# R3D2_long_range.net
KiCad netlist of a schematic drawn in EAGLE
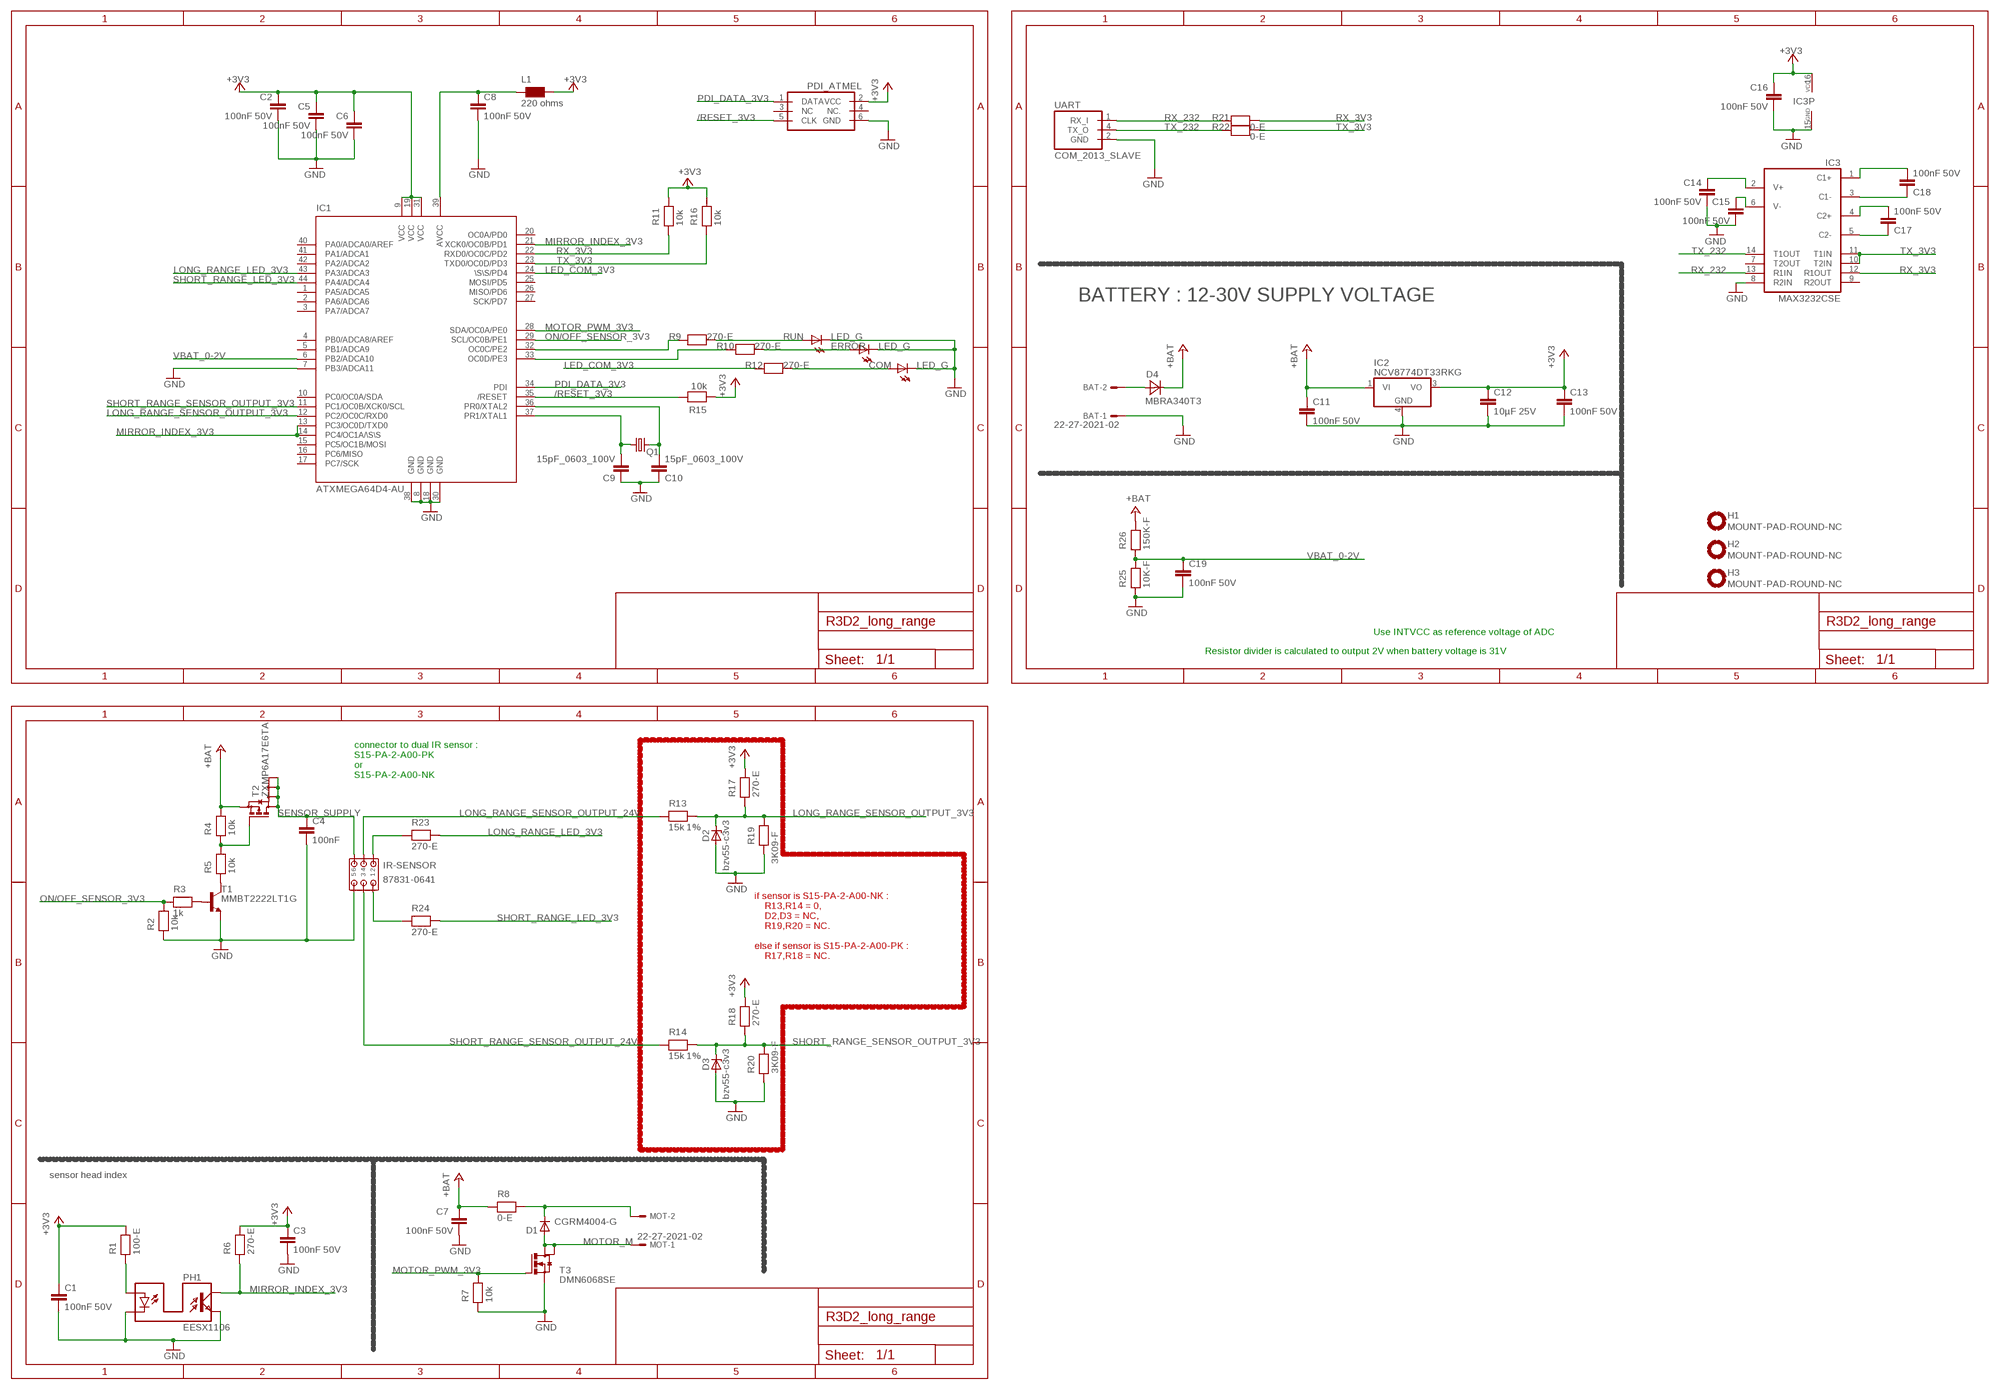
[diagram p0: schematic, sheet 1]

(export (version "E")
  (design (tool "Eeschema 10.0.6"))
  (components
    (comp (ref "BAT")
      (value "22-27-2021-02")
      (footprint "eagle-import:6410-02")
      (libsource (lib "eagle-import") (part "22-?-0227-2021"))
    )
    (comp (ref "C1")
      (value "100nF 50V")
      (footprint "eagle-import:C0603")
      (libsource (lib "eagle-import") (part "100NF-F"))
    )
    (comp (ref "C2")
      (value "100nF 50V")
      (footprint "eagle-import:C0603")
      (libsource (lib "eagle-import") (part "100NF-F"))
    )
    (comp (ref "C3")
      (value "100nF 50V")
      (footprint "eagle-import:C0603")
      (libsource (lib "eagle-import") (part "100NF-F"))
    )
    (comp (ref "C4")
      (value "100nF")
      (footprint "eagle-import:C0603")
      (libsource (lib "eagle-import") (part "100NF-F"))
    )
    (comp (ref "C5")
      (value "100nF 50V")
      (footprint "eagle-import:C0603")
      (libsource (lib "eagle-import") (part "100NF-F"))
    )
    (comp (ref "C6")
      (value "100nF 50V")
      (footprint "eagle-import:C0603")
      (libsource (lib "eagle-import") (part "100NF-F"))
    )
    (comp (ref "C7")
      (value "100nF 50V")
      (footprint "eagle-import:C0603")
      (libsource (lib "eagle-import") (part "100NF-F"))
    )
    (comp (ref "C8")
      (value "100nF 50V")
      (footprint "eagle-import:C0603")
      (libsource (lib "eagle-import") (part "100NF-F"))
    )
    (comp (ref "C9")
      (value "15pF_0603_100V")
      (footprint "eagle-import:C0603")
      (libsource (lib "eagle-import") (part "15PF-F"))
    )
    (comp (ref "C10")
      (value "15pF_0603_100V")
      (footprint "eagle-import:C0603")
      (libsource (lib "eagle-import") (part "15PF-F"))
    )
    (comp (ref "C11")
      (value "100nF 50V")
      (footprint "eagle-import:C0805")
      (libsource (lib "eagle-import") (part "100NF-E"))
    )
    (comp (ref "C12")
      (value "10µF 25V")
      (footprint "eagle-import:C1210")
      (libsource (lib "eagle-import") (part "10UF-C_25V"))
    )
    (comp (ref "C13")
      (value "100nF 50V")
      (footprint "eagle-import:C0603")
      (libsource (lib "eagle-import") (part "100NF-F"))
    )
    (comp (ref "C14")
      (value "100nF 50V")
      (footprint "eagle-import:C0603")
      (libsource (lib "eagle-import") (part "100NF-F"))
    )
    (comp (ref "C15")
      (value "100nF 50V")
      (footprint "eagle-import:C0603")
      (libsource (lib "eagle-import") (part "100NF-F"))
    )
    (comp (ref "C16")
      (value "100nF 50V")
      (footprint "eagle-import:C0603")
      (libsource (lib "eagle-import") (part "100NF-F"))
    )
    (comp (ref "C17")
      (value "100nF 50V")
      (footprint "eagle-import:C0603")
      (libsource (lib "eagle-import") (part "100NF-F"))
    )
    (comp (ref "C18")
      (value "100nF 50V")
      (footprint "eagle-import:C0603")
      (libsource (lib "eagle-import") (part "100NF-F"))
    )
    (comp (ref "C19")
      (value "100nF 50V")
      (footprint "eagle-import:C0805")
      (libsource (lib "eagle-import") (part "100NF-E"))
    )
    (comp (ref "COM")
      (value "LED_G")
      (footprint "eagle-import:CHIP-LED0805")
      (libsource (lib "eagle-import") (part "LED_G"))
    )
    (comp (ref "D1")
      (value "CGRM4004-G")
      (footprint "eagle-import:SOD-123_MINI-SMA")
      (libsource (lib "eagle-import") (part "CGRM400-G4"))
    )
    (comp (ref "D2")
      (value "bzv55-c3v3")
      (footprint "eagle-import:SOD80C")
      (libsource (lib "eagle-import") (part "BZV55-C3V3SOD80C"))
    )
    (comp (ref "D3")
      (value "bzv55-c3v3")
      (footprint "eagle-import:SOD80C")
      (libsource (lib "eagle-import") (part "BZV55-C3V3SOD80C"))
    )
    (comp (ref "D4")
      (value "MBRA340T3")
      (footprint "eagle-import:SMA")
      (libsource (lib "eagle-import") (part "MBRA340T3"))
    )
    (comp (ref "ERROR")
      (value "LED_G")
      (footprint "eagle-import:CHIP-LED0805")
      (libsource (lib "eagle-import") (part "LED_G"))
    )
    (comp (ref "H1")
      (value "MOUNT-PAD-ROUND-NC")
      (footprint "eagle-import:3,0-PAD_NC")
      (libsource (lib "eagle-import") (part "MOUNT-PAD-ROUND-NC"))
    )
    (comp (ref "H2")
      (value "MOUNT-PAD-ROUND-NC")
      (footprint "eagle-import:3,0-PAD_NC")
      (libsource (lib "eagle-import") (part "MOUNT-PAD-ROUND-NC"))
    )
    (comp (ref "H3")
      (value "MOUNT-PAD-ROUND-NC")
      (footprint "eagle-import:3,0-PAD_NC")
      (libsource (lib "eagle-import") (part "MOUNT-PAD-ROUND-NC"))
    )
    (comp (ref "IC1")
      (value "ATXMEGA64D4-AU")
      (footprint "eagle-import:TQFP44")
      (libsource (lib "eagle-import") (part "ATXMEGA64D4-AU"))
    )
    (comp (ref "IC2")
      (value "NCV8774DT33RKG")
      (footprint "eagle-import:DPACK_3")
      (libsource (lib "eagle-import") (part "NCV8774DT33RKG"))
    )
    (comp (ref "IC3")
      (value "MAX3232CSE")
      (footprint "eagle-import:SO16")
      (libsource (lib "eagle-import") (part "MAX3232SEC"))
    )
    (comp (ref "IR-SENSOR")
      (value "87831-0641")
      (footprint "eagle-import:87831-0641")
      (libsource (lib "eagle-import") (part "87831-0641"))
    )
    (comp (ref "L1")
      (value "220 ohms")
      (footprint "eagle-import:R0603")
      (libsource (lib "eagle-import") (part "FERRITE_220OHMS"))
    )
    (comp (ref "MOT")
      (value "22-27-2021-02")
      (footprint "eagle-import:6410-02")
      (libsource (lib "eagle-import") (part "22-?-0227-2021"))
    )
    (comp (ref "PDI_ATMEL")
      (value "PDI_ATMELL")
      (footprint "eagle-import:ML6L")
      (libsource (lib "eagle-import") (part "PDI_ATMELL"))
    )
    (comp (ref "PH1")
      (value "EESX1106")
      (footprint "eagle-import:EESX1106")
      (libsource (lib "eagle-import") (part "EESX1106"))
    )
    (comp (ref "Q1")
      (value "CRYSTAL_16MHZ_5032")
      (footprint "eagle-import:CRYSTAL_5032")
      (libsource (lib "eagle-import") (part "CRYSTAL_16MHZ_5032"))
    )
    (comp (ref "R1")
      (value "100-E")
      (footprint "eagle-import:R0805")
      (libsource (lib "eagle-import") (part "100-E"))
    )
    (comp (ref "R2")
      (value "10k")
      (footprint "eagle-import:R0603")
      (libsource (lib "eagle-import") (part "10K-F"))
    )
    (comp (ref "R3")
      (value "1k")
      (footprint "eagle-import:R0603")
      (libsource (lib "eagle-import") (part "1K-F"))
    )
    (comp (ref "R4")
      (value "10k")
      (footprint "eagle-import:R0603")
      (libsource (lib "eagle-import") (part "10K-F"))
    )
    (comp (ref "R5")
      (value "10k")
      (footprint "eagle-import:R0603")
      (libsource (lib "eagle-import") (part "10K-F"))
    )
    (comp (ref "R6")
      (value "270-E")
      (footprint "eagle-import:R0805")
      (libsource (lib "eagle-import") (part "270-E"))
    )
    (comp (ref "R7")
      (value "10k")
      (footprint "eagle-import:R0603")
      (libsource (lib "eagle-import") (part "10K-F"))
    )
    (comp (ref "R8")
      (value "0-E")
      (footprint "eagle-import:R0805")
      (libsource (lib "eagle-import") (part "0-E"))
    )
    (comp (ref "R9")
      (value "270-E")
      (footprint "eagle-import:R0805")
      (libsource (lib "eagle-import") (part "270-E"))
    )
    (comp (ref "R10")
      (value "270-E")
      (footprint "eagle-import:R0805")
      (libsource (lib "eagle-import") (part "270-E"))
    )
    (comp (ref "R11")
      (value "10k")
      (footprint "eagle-import:R0603")
      (libsource (lib "eagle-import") (part "10K-F"))
    )
    (comp (ref "R12")
      (value "270-E")
      (footprint "eagle-import:R0805")
      (libsource (lib "eagle-import") (part "270-E"))
    )
    (comp (ref "R13")
      (value "15k 1%")
      (footprint "eagle-import:R0603")
      (libsource (lib "eagle-import") (part "15K-F"))
    )
    (comp (ref "R14")
      (value "15k 1%")
      (footprint "eagle-import:R0603")
      (libsource (lib "eagle-import") (part "15K-F"))
    )
    (comp (ref "R15")
      (value "10k")
      (footprint "eagle-import:R0603")
      (libsource (lib "eagle-import") (part "10K-F"))
    )
    (comp (ref "R16")
      (value "10k")
      (footprint "eagle-import:R0603")
      (libsource (lib "eagle-import") (part "10K-F"))
    )
    (comp (ref "R17")
      (value "270-E")
      (footprint "eagle-import:R0805")
      (libsource (lib "eagle-import") (part "270-E"))
    )
    (comp (ref "R18")
      (value "270-E")
      (footprint "eagle-import:R0805")
      (libsource (lib "eagle-import") (part "270-E"))
    )
    (comp (ref "R19")
      (value "3K09-F")
      (footprint "eagle-import:R0603")
      (libsource (lib "eagle-import") (part "3K09-F"))
    )
    (comp (ref "R20")
      (value "3K09-F")
      (footprint "eagle-import:R0603")
      (libsource (lib "eagle-import") (part "3K09-F"))
    )
    (comp (ref "R21")
      (value "0-E")
      (footprint "eagle-import:R0805")
      (libsource (lib "eagle-import") (part "0-E"))
    )
    (comp (ref "R22")
      (value "0-E")
      (footprint "eagle-import:R0805")
      (libsource (lib "eagle-import") (part "0-E"))
    )
    (comp (ref "R23")
      (value "270-E")
      (footprint "eagle-import:R0805")
      (libsource (lib "eagle-import") (part "270-E"))
    )
    (comp (ref "R24")
      (value "270-E")
      (footprint "eagle-import:R0805")
      (libsource (lib "eagle-import") (part "270-E"))
    )
    (comp (ref "R25")
      (value "10K-F")
      (footprint "eagle-import:R0603")
      (libsource (lib "eagle-import") (part "10K-F"))
    )
    (comp (ref "R26")
      (value "150K-F")
      (footprint "eagle-import:R0603")
      (libsource (lib "eagle-import") (part "150K-F"))
    )
    (comp (ref "RUN")
      (value "LED_G")
      (footprint "eagle-import:CHIP-LED0805")
      (libsource (lib "eagle-import") (part "LED_G"))
    )
    (comp (ref "T1")
      (value "MMBT2222LT1G")
      (footprint "eagle-import:SOT23-BEC")
      (libsource (lib "eagle-import") (part "-NPN-SOT23-BECMMBT2222ALT1"))
    )
    (comp (ref "T2")
      (value "ZXMP6A17E6TA")
      (footprint "eagle-import:SOT26")
      (libsource (lib "eagle-import") (part "ZXMP6A17E6TA"))
    )
    (comp (ref "T3")
      (value "DMN6068SE")
      (footprint "eagle-import:SOT223")
      (libsource (lib "eagle-import") (part "DMN6068SE"))
    )
    (comp (ref "UART")
      (value "COM_2013_SLAVE")
      (footprint "eagle-import:MICROMATCH-4_SMD")
      (libsource (lib "eagle-import") (part "COM_2013_SLAVE"))
    )
  )
  (nets
    (net (code "1") (name "+3V3") (class "Default")
      (node (ref "C1") (pin "1") (pinfunction "1_1") (pintype "passive"))
      (node (ref "C12") (pin "1") (pinfunction "1_1") (pintype "passive"))
      (node (ref "C13") (pin "1") (pinfunction "1_1") (pintype "passive"))
      (node (ref "C16") (pin "1") (pinfunction "1_1") (pintype "passive"))
      (node (ref "C2") (pin "1") (pinfunction "1_1") (pintype "passive"))
      (node (ref "C3") (pin "1") (pinfunction "1_1") (pintype "passive"))
      (node (ref "C5") (pin "1") (pinfunction "1_1") (pintype "passive"))
      (node (ref "C6") (pin "1") (pinfunction "1_1") (pintype "passive"))
      (node (ref "IC1") (pin "19") (pinfunction "VCC_19") (pintype "bidirectional"))
      (node (ref "IC1") (pin "31") (pinfunction "VCC_31") (pintype "bidirectional"))
      (node (ref "IC1") (pin "9") (pinfunction "VCC_9") (pintype "bidirectional"))
      (node (ref "IC2") (pin "3") (pinfunction "VO_3") (pintype "passive"))
      (node (ref "IC3") (pin "16") (pinfunction "VCC_16") (pintype "power_in"))
      (node (ref "L1") (pin "2") (pinfunction "2_2") (pintype "passive"))
      (node (ref "PDI_ATMEL") (pin "2") (pinfunction "VCC_2") (pintype "passive"))
      (node (ref "R1") (pin "2") (pinfunction "2_2") (pintype "bidirectional"))
      (node (ref "R11") (pin "2") (pinfunction "2_2") (pintype "bidirectional"))
      (node (ref "R15") (pin "1") (pinfunction "1_1") (pintype "bidirectional"))
      (node (ref "R16") (pin "2") (pinfunction "2_2") (pintype "bidirectional"))
      (node (ref "R17") (pin "2") (pinfunction "2_2") (pintype "bidirectional"))
      (node (ref "R18") (pin "2") (pinfunction "2_2") (pintype "bidirectional"))
      (node (ref "R6") (pin "2") (pinfunction "2_2") (pintype "bidirectional"))
    )
    (net (code "2") (name "+BAT") (class "Default")
      (node (ref "C11") (pin "1") (pinfunction "1_1") (pintype "passive"))
      (node (ref "C7") (pin "1") (pinfunction "1_1") (pintype "passive"))
      (node (ref "D4") (pin "C") (pinfunction "C_C") (pintype "passive"))
      (node (ref "IC2") (pin "1") (pinfunction "VI_1") (pintype "input"))
      (node (ref "R26") (pin "2") (pinfunction "2_2") (pintype "bidirectional"))
      (node (ref "R4") (pin "2") (pinfunction "2_2") (pintype "bidirectional"))
      (node (ref "R8") (pin "1") (pinfunction "1_1") (pintype "bidirectional"))
      (node (ref "T2") (pin "4") (pinfunction "S_4") (pintype "passive"))
    )
    (net (code "3") (name "/LED_COM_3V3") (class "Default")
      (node (ref "IC1") (pin "24") (pinfunction "\\S\\S/PD4_24") (pintype "bidirectional"))
      (node (ref "R12") (pin "1") (pinfunction "1_1") (pintype "bidirectional"))
    )
    (net (code "4") (name "/LONG_RANGE_LED_3V3") (class "Default")
      (node (ref "IC1") (pin "43") (pinfunction "PA3/ADCA3_43") (pintype "bidirectional"))
      (node (ref "R23") (pin "2") (pinfunction "2_2") (pintype "bidirectional"))
    )
    (net (code "5") (name "/LONG_RANGE_SENSOR_OUTPUT_3V3") (class "Default")
      (node (ref "D2") (pin "C") (pinfunction "C_C") (pintype "passive"))
      (node (ref "IC1") (pin "12") (pinfunction "PC2/OC0C/RXD0_12") (pintype "bidirectional"))
      (node (ref "R13") (pin "2") (pinfunction "2_2") (pintype "bidirectional"))
      (node (ref "R17") (pin "1") (pinfunction "1_1") (pintype "bidirectional"))
      (node (ref "R19") (pin "2") (pinfunction "2_2") (pintype "bidirectional"))
    )
    (net (code "6") (name "/LONG_RANGE_SENSOR_OUTPUT_24V") (class "Default")
      (node (ref "IR-SENSOR") (pin "4") (pinfunction "4_4") (pintype "passive"))
      (node (ref "R13") (pin "1") (pinfunction "1_1") (pintype "bidirectional"))
    )
    (net (code "7") (name "/MIRROR_INDEX_3V3") (class "Default")
      (node (ref "IC1") (pin "13") (pinfunction "PC3/OC0D/TXD0_13") (pintype "bidirectional"))
      (node (ref "IC1") (pin "14") (pinfunction "PC4/OC1A/\\S\\S_14") (pintype "bidirectional"))
      (node (ref "IC1") (pin "21") (pinfunction "XCK0/OC0B/PD1_21") (pintype "bidirectional"))
      (node (ref "PH1") (pin "C") (pinfunction "TRANSISTOR_C_C") (pintype "passive"))
      (node (ref "R6") (pin "1") (pinfunction "1_1") (pintype "bidirectional"))
    )
    (net (code "8") (name "/MOTOR_M") (class "Default")
      (node (ref "D1") (pin "A") (pinfunction "A_A") (pintype "passive"))
      (node (ref "MOT") (pin "1") (pinfunction "S_1") (pintype "passive"))
      (node (ref "T3") (pin "2") (pinfunction "D_2") (pintype "passive"))
      (node (ref "T3") (pin "4") (pinfunction "D_4") (pintype "passive"))
    )
    (net (code "9") (name "/MOTOR_PWM_3V3") (class "Default")
      (node (ref "IC1") (pin "28") (pinfunction "SDA/OC0A/PE0_28") (pintype "bidirectional"))
      (node (ref "R7") (pin "2") (pinfunction "2_2") (pintype "bidirectional"))
      (node (ref "T3") (pin "1") (pinfunction "G_1") (pintype "passive"))
    )
    (net (code "10") (name "/ON{slash}OFF_SENSOR_3V3") (class "Default")
      (node (ref "IC1") (pin "29") (pinfunction "SCL/OC0B/PE1_29") (pintype "bidirectional"))
      (node (ref "R2") (pin "2") (pinfunction "2_2") (pintype "bidirectional"))
      (node (ref "R3") (pin "1") (pinfunction "1_1") (pintype "bidirectional"))
    )
    (net (code "11") (name "/PDI_DATA_3V3") (class "Default")
      (node (ref "IC1") (pin "34") (pinfunction "PDI_34") (pintype "bidirectional"))
      (node (ref "PDI_ATMEL") (pin "1") (pinfunction "DATA_1") (pintype "passive"))
    )
    (net (code "12") (name "/RX_3V3") (class "Default")
      (node (ref "IC1") (pin "22") (pinfunction "RXD0/OC0C/PD2_22") (pintype "bidirectional"))
      (node (ref "IC3") (pin "12") (pinfunction "R1OUT_12") (pintype "output"))
      (node (ref "R11") (pin "1") (pinfunction "1_1") (pintype "bidirectional"))
      (node (ref "R21") (pin "2") (pinfunction "2_2") (pintype "bidirectional"))
    )
    (net (code "13") (name "/RX_232") (class "Default")
      (node (ref "IC3") (pin "13") (pinfunction "R1IN_13") (pintype "input"))
      (node (ref "R21") (pin "1") (pinfunction "1_1") (pintype "bidirectional"))
      (node (ref "UART") (pin "1") (pinfunction "RX_I_1") (pintype "passive"))
    )
    (net (code "14") (name "/SENSOR_SUPPLY") (class "Default")
      (node (ref "C4") (pin "1") (pinfunction "1_1") (pintype "passive"))
      (node (ref "IR-SENSOR") (pin "6") (pinfunction "6_6") (pintype "passive"))
      (node (ref "T2") (pin "1") (pinfunction "D_1") (pintype "passive"))
      (node (ref "T2") (pin "2") (pinfunction "D_2") (pintype "passive"))
      (node (ref "T2") (pin "5") (pinfunction "D_5") (pintype "passive"))
      (node (ref "T2") (pin "6") (pinfunction "D_6") (pintype "passive"))
    )
    (net (code "15") (name "/SHORT_RANGE_LED_3V3") (class "Default")
      (node (ref "IC1") (pin "44") (pinfunction "PA4/ADCA4_44") (pintype "bidirectional"))
      (node (ref "R24") (pin "2") (pinfunction "2_2") (pintype "bidirectional"))
    )
    (net (code "16") (name "/SHORT_RANGE_SENSOR_OUTPUT_3V3") (class "Default")
      (node (ref "D3") (pin "C") (pinfunction "C_C") (pintype "passive"))
      (node (ref "IC1") (pin "11") (pinfunction "PC1/OC0B/XCK0/SCL_11") (pintype "bidirectional"))
      (node (ref "R14") (pin "2") (pinfunction "2_2") (pintype "bidirectional"))
      (node (ref "R18") (pin "1") (pinfunction "1_1") (pintype "bidirectional"))
      (node (ref "R20") (pin "2") (pinfunction "2_2") (pintype "bidirectional"))
    )
    (net (code "17") (name "/SHORT_RANGE_SENSOR_OUTPUT_24V") (class "Default")
      (node (ref "IR-SENSOR") (pin "3") (pinfunction "3_3") (pintype "passive"))
      (node (ref "R14") (pin "1") (pinfunction "1_1") (pintype "bidirectional"))
    )
    (net (code "18") (name "/TX_3V3") (class "Default")
      (node (ref "IC1") (pin "23") (pinfunction "TXD0/OC0D/PD3_23") (pintype "bidirectional"))
      (node (ref "IC3") (pin "10") (pinfunction "T2IN_10") (pintype "input"))
      (node (ref "IC3") (pin "11") (pinfunction "T1IN_11") (pintype "input"))
      (node (ref "R16") (pin "1") (pinfunction "1_1") (pintype "bidirectional"))
      (node (ref "R22") (pin "2") (pinfunction "2_2") (pintype "bidirectional"))
    )
    (net (code "19") (name "/TX_232") (class "Default")
      (node (ref "IC3") (pin "14") (pinfunction "T1OUT_14") (pintype "output"))
      (node (ref "R22") (pin "1") (pinfunction "1_1") (pintype "bidirectional"))
      (node (ref "UART") (pin "4") (pinfunction "TX_O_4") (pintype "passive"))
    )
    (net (code "20") (name "/VBAT_0-2V") (class "Default")
      (node (ref "C19") (pin "1") (pinfunction "1_1") (pintype "passive"))
      (node (ref "IC1") (pin "6") (pinfunction "PB2/ADCA10_6") (pintype "bidirectional"))
      (node (ref "R25") (pin "2") (pinfunction "2_2") (pintype "bidirectional"))
      (node (ref "R26") (pin "1") (pinfunction "1_1") (pintype "bidirectional"))
    )
    (net (code "21") (name "/{slash}RESET_3V3") (class "Default")
      (node (ref "IC1") (pin "35") (pinfunction "/RESET_35") (pintype "bidirectional"))
      (node (ref "PDI_ATMEL") (pin "5") (pinfunction "CLK_5") (pintype "passive"))
      (node (ref "R15") (pin "2") (pinfunction "2_2") (pintype "bidirectional"))
    )
    (net (code "22") (name "GND") (class "Default")
      (node (ref "BAT") (pin "1") (pinfunction "S_1") (pintype "passive"))
      (node (ref "C1") (pin "2") (pinfunction "2_2") (pintype "passive"))
      (node (ref "C10") (pin "1") (pinfunction "1_1") (pintype "passive"))
      (node (ref "C11") (pin "2") (pinfunction "2_2") (pintype "passive"))
      (node (ref "C12") (pin "2") (pinfunction "2_2") (pintype "passive"))
      (node (ref "C13") (pin "2") (pinfunction "2_2") (pintype "passive"))
      (node (ref "C14") (pin "2") (pinfunction "2_2") (pintype "passive"))
      (node (ref "C15") (pin "2") (pinfunction "2_2") (pintype "passive"))
      (node (ref "C16") (pin "2") (pinfunction "2_2") (pintype "passive"))
      (node (ref "C19") (pin "2") (pinfunction "2_2") (pintype "passive"))
      (node (ref "C2") (pin "2") (pinfunction "2_2") (pintype "passive"))
      (node (ref "C3") (pin "2") (pinfunction "2_2") (pintype "passive"))
      (node (ref "C4") (pin "2") (pinfunction "2_2") (pintype "passive"))
      (node (ref "C5") (pin "2") (pinfunction "2_2") (pintype "passive"))
      (node (ref "C6") (pin "2") (pinfunction "2_2") (pintype "passive"))
      (node (ref "C7") (pin "2") (pinfunction "2_2") (pintype "passive"))
      (node (ref "C8") (pin "2") (pinfunction "2_2") (pintype "passive"))
      (node (ref "C9") (pin "1") (pinfunction "1_1") (pintype "passive"))
      (node (ref "COM") (pin "C") (pinfunction "C_C") (pintype "passive"))
      (node (ref "D2") (pin "A") (pinfunction "A_A") (pintype "passive"))
      (node (ref "D3") (pin "A") (pinfunction "A_A") (pintype "passive"))
      (node (ref "ERROR") (pin "C") (pinfunction "C_C") (pintype "passive"))
      (node (ref "IC1") (pin "18") (pinfunction "GND_18") (pintype "bidirectional"))
      (node (ref "IC1") (pin "30") (pinfunction "GND_30") (pintype "bidirectional"))
      (node (ref "IC1") (pin "38") (pinfunction "GND_38") (pintype "bidirectional"))
      (node (ref "IC1") (pin "7") (pinfunction "PB3/ADCA11_7") (pintype "bidirectional"))
      (node (ref "IC1") (pin "8") (pinfunction "GND_8") (pintype "bidirectional"))
      (node (ref "IC2") (pin "4") (pinfunction "GND_4") (pintype "passive"))
      (node (ref "IC3") (pin "15") (pinfunction "GND_15") (pintype "power_in"))
      (node (ref "IC3") (pin "8") (pinfunction "R2IN_8") (pintype "input"))
      (node (ref "IR-SENSOR") (pin "5") (pinfunction "5_5") (pintype "passive"))
      (node (ref "PDI_ATMEL") (pin "6") (pinfunction "GND_6") (pintype "passive"))
      (node (ref "PH1") (pin "E") (pinfunction "TRANSISTOR_E_E") (pintype "passive"))
      (node (ref "PH1") (pin "K") (pinfunction "LED_C_K") (pintype "passive"))
      (node (ref "R19") (pin "1") (pinfunction "1_1") (pintype "bidirectional"))
      (node (ref "R2") (pin "1") (pinfunction "1_1") (pintype "bidirectional"))
      (node (ref "R20") (pin "1") (pinfunction "1_1") (pintype "bidirectional"))
      (node (ref "R25") (pin "1") (pinfunction "1_1") (pintype "bidirectional"))
      (node (ref "R7") (pin "1") (pinfunction "1_1") (pintype "bidirectional"))
      (node (ref "RUN") (pin "C") (pinfunction "C_C") (pintype "passive"))
      (node (ref "T1") (pin "E") (pinfunction "E_E") (pintype "passive"))
      (node (ref "T3") (pin "3") (pinfunction "S_3") (pintype "passive"))
      (node (ref "UART") (pin "2") (pinfunction "GND_2") (pintype "passive"))
    )
    (net (code "23") (name "Net-(BATB-S)") (class "Default")
      (node (ref "BAT") (pin "2") (pinfunction "S_2") (pintype "passive"))
      (node (ref "D4") (pin "A") (pinfunction "A_A") (pintype "passive"))
    )
    (net (code "24") (name "Net-(COM-PadA)") (class "Default")
      (node (ref "COM") (pin "A") (pinfunction "A_A") (pintype "passive"))
      (node (ref "R12") (pin "2") (pinfunction "2_2") (pintype "bidirectional"))
    )
    (net (code "25") (name "Net-(ERROR-PadA)") (class "Default")
      (node (ref "ERROR") (pin "A") (pinfunction "A_A") (pintype "passive"))
      (node (ref "R10") (pin "2") (pinfunction "2_2") (pintype "bidirectional"))
    )
    (net (code "26") (name "Net-(IC1-AVCC)") (class "Default")
      (node (ref "C8") (pin "1") (pinfunction "1_1") (pintype "passive"))
      (node (ref "IC1") (pin "39") (pinfunction "AVCC_39") (pintype "bidirectional"))
      (node (ref "L1") (pin "1") (pinfunction "1_1") (pintype "passive"))
    )
    (net (code "27") (name "Net-(IC1-OC0C{slash}PE2)") (class "Default")
      (node (ref "IC1") (pin "32") (pinfunction "OC0C/PE2_32") (pintype "bidirectional"))
      (node (ref "R9") (pin "1") (pinfunction "1_1") (pintype "bidirectional"))
    )
    (net (code "28") (name "Net-(IC1-OC0D{slash}PE3)") (class "Default")
      (node (ref "IC1") (pin "33") (pinfunction "OC0D/PE3_33") (pintype "bidirectional"))
      (node (ref "R10") (pin "1") (pinfunction "1_1") (pintype "bidirectional"))
    )
    (net (code "29") (name "Net-(IC1-PR0{slash}XTAL2)") (class "Default")
      (node (ref "C10") (pin "2") (pinfunction "2_2") (pintype "passive"))
      (node (ref "IC1") (pin "36") (pinfunction "PR0/XTAL2_36") (pintype "bidirectional"))
      (node (ref "Q1") (pin "2") (pinfunction "2_2") (pintype "passive"))
    )
    (net (code "30") (name "Net-(IC1-PR1{slash}XTAL1)") (class "Default")
      (node (ref "C9") (pin "2") (pinfunction "2_2") (pintype "passive"))
      (node (ref "IC1") (pin "37") (pinfunction "PR1/XTAL1_37") (pintype "bidirectional"))
      (node (ref "Q1") (pin "1") (pinfunction "1_1") (pintype "passive"))
    )
    (net (code "31") (name "Net-(IC3A-C1+)") (class "Default")
      (node (ref "C18") (pin "1") (pinfunction "1_1") (pintype "passive"))
      (node (ref "IC3") (pin "1") (pinfunction "C1+_1") (pintype "bidirectional"))
    )
    (net (code "32") (name "Net-(IC3A-C1-)") (class "Default")
      (node (ref "C18") (pin "2") (pinfunction "2_2") (pintype "passive"))
      (node (ref "IC3") (pin "3") (pinfunction "C1-_3") (pintype "bidirectional"))
    )
    (net (code "33") (name "Net-(IC3A-C2+)") (class "Default")
      (node (ref "C17") (pin "1") (pinfunction "1_1") (pintype "passive"))
      (node (ref "IC3") (pin "4") (pinfunction "C2+_4") (pintype "bidirectional"))
    )
    (net (code "34") (name "Net-(IC3A-C2-)") (class "Default")
      (node (ref "C17") (pin "2") (pinfunction "2_2") (pintype "passive"))
      (node (ref "IC3") (pin "5") (pinfunction "C2-_5") (pintype "bidirectional"))
    )
    (net (code "35") (name "Net-(IC3A-V+)") (class "Default")
      (node (ref "C14") (pin "1") (pinfunction "1_1") (pintype "passive"))
      (node (ref "IC3") (pin "2") (pinfunction "V+_2") (pintype "bidirectional"))
    )
    (net (code "36") (name "Net-(IC3A-V-)") (class "Default")
      (node (ref "C15") (pin "1") (pinfunction "1_1") (pintype "passive"))
      (node (ref "IC3") (pin "6") (pinfunction "V-_6") (pintype "bidirectional"))
    )
    (net (code "37") (name "Net-(IR-SENSOR-Pad1)") (class "Default")
      (node (ref "IR-SENSOR") (pin "1") (pinfunction "1_1") (pintype "passive"))
      (node (ref "R24") (pin "1") (pinfunction "1_1") (pintype "bidirectional"))
    )
    (net (code "38") (name "Net-(IR-SENSOR-Pad2)") (class "Default")
      (node (ref "IR-SENSOR") (pin "2") (pinfunction "2_2") (pintype "passive"))
      (node (ref "R23") (pin "1") (pinfunction "1_1") (pintype "bidirectional"))
    )
    (net (code "39") (name "Net-(MOTB-S)") (class "Default")
      (node (ref "D1") (pin "C") (pinfunction "C_C") (pintype "passive"))
      (node (ref "MOT") (pin "2") (pinfunction "S_2") (pintype "passive"))
      (node (ref "R8") (pin "2") (pinfunction "2_2") (pintype "bidirectional"))
    )
    (net (code "40") (name "Net-(PH1-LED_A)") (class "Default")
      (node (ref "PH1") (pin "A") (pinfunction "LED_A_A") (pintype "passive"))
      (node (ref "R1") (pin "1") (pinfunction "1_1") (pintype "bidirectional"))
    )
    (net (code "41") (name "Net-(R3-Pad2)") (class "Default")
      (node (ref "R3") (pin "2") (pinfunction "2_2") (pintype "bidirectional"))
      (node (ref "T1") (pin "B") (pinfunction "B_B") (pintype "passive"))
    )
    (net (code "42") (name "Net-(R5-Pad1)") (class "Default")
      (node (ref "R5") (pin "1") (pinfunction "1_1") (pintype "bidirectional"))
      (node (ref "T1") (pin "C") (pinfunction "C_C") (pintype "passive"))
    )
    (net (code "43") (name "Net-(R9-Pad2)") (class "Default")
      (node (ref "R9") (pin "2") (pinfunction "2_2") (pintype "bidirectional"))
      (node (ref "RUN") (pin "A") (pinfunction "A_A") (pintype "passive"))
    )
    (net (code "44") (name "Net-(T2-G)") (class "Default")
      (node (ref "R4") (pin "1") (pinfunction "1_1") (pintype "bidirectional"))
      (node (ref "R5") (pin "2") (pinfunction "2_2") (pintype "bidirectional"))
      (node (ref "T2") (pin "3") (pinfunction "G_3") (pintype "passive"))
    )
    (net (code "45") (name "unconnected-(IC1-MISO{slash}PD6-Pad26)") (class "Default")
      (node (ref "IC1") (pin "26") (pinfunction "MISO/PD6_26") (pintype "bidirectional"))
    )
    (net (code "46") (name "unconnected-(IC1-MOSI{slash}PD5-Pad25)") (class "Default")
      (node (ref "IC1") (pin "25") (pinfunction "MOSI/PD5_25") (pintype "bidirectional"))
    )
    (net (code "47") (name "unconnected-(IC1-OC0A{slash}PD0-Pad20)") (class "Default")
      (node (ref "IC1") (pin "20") (pinfunction "OC0A/PD0_20") (pintype "bidirectional"))
    )
    (net (code "48") (name "unconnected-(IC1-PA0{slash}ADCA0{slash}AREF-Pad40)") (class "Default")
      (node (ref "IC1") (pin "40") (pinfunction "PA0/ADCA0/AREF_40") (pintype "bidirectional"))
    )
    (net (code "49") (name "unconnected-(IC1-PA1{slash}ADCA1-Pad41)") (class "Default")
      (node (ref "IC1") (pin "41") (pinfunction "PA1/ADCA1_41") (pintype "bidirectional"))
    )
    (net (code "50") (name "unconnected-(IC1-PA2{slash}ADCA2-Pad42)") (class "Default")
      (node (ref "IC1") (pin "42") (pinfunction "PA2/ADCA2_42") (pintype "bidirectional"))
    )
    (net (code "51") (name "unconnected-(IC1-PA5{slash}ADCA5-Pad1)") (class "Default")
      (node (ref "IC1") (pin "1") (pinfunction "PA5/ADCA5_1") (pintype "bidirectional"))
    )
    (net (code "52") (name "unconnected-(IC1-PA6{slash}ADCA6-Pad2)") (class "Default")
      (node (ref "IC1") (pin "2") (pinfunction "PA6/ADCA6_2") (pintype "bidirectional"))
    )
    (net (code "53") (name "unconnected-(IC1-PA7{slash}ADCA7-Pad3)") (class "Default")
      (node (ref "IC1") (pin "3") (pinfunction "PA7/ADCA7_3") (pintype "bidirectional"))
    )
    (net (code "54") (name "unconnected-(IC1-PB0{slash}ADCA8{slash}AREF-Pad4)") (class "Default")
      (node (ref "IC1") (pin "4") (pinfunction "PB0/ADCA8/AREF_4") (pintype "bidirectional"))
    )
    (net (code "55") (name "unconnected-(IC1-PB1{slash}ADCA9-Pad5)") (class "Default")
      (node (ref "IC1") (pin "5") (pinfunction "PB1/ADCA9_5") (pintype "bidirectional"))
    )
    (net (code "56") (name "unconnected-(IC1-PC0{slash}OC0A{slash}SDA-Pad10)") (class "Default")
      (node (ref "IC1") (pin "10") (pinfunction "PC0/OC0A/SDA_10") (pintype "bidirectional"))
    )
    (net (code "57") (name "unconnected-(IC1-PC5{slash}OC1B{slash}MOSI-Pad15)") (class "Default")
      (node (ref "IC1") (pin "15") (pinfunction "PC5/OC1B/MOSI_15") (pintype "bidirectional"))
    )
    (net (code "58") (name "unconnected-(IC1-PC6{slash}MISO-Pad16)") (class "Default")
      (node (ref "IC1") (pin "16") (pinfunction "PC6/MISO_16") (pintype "bidirectional"))
    )
    (net (code "59") (name "unconnected-(IC1-PC7{slash}SCK-Pad17)") (class "Default")
      (node (ref "IC1") (pin "17") (pinfunction "PC7/SCK_17") (pintype "bidirectional"))
    )
    (net (code "60") (name "unconnected-(IC1-SCK{slash}PD7-Pad27)") (class "Default")
      (node (ref "IC1") (pin "27") (pinfunction "SCK/PD7_27") (pintype "bidirectional"))
    )
    (net (code "61") (name "unconnected-(IC3A-R2OUT-Pad9)") (class "Default")
      (node (ref "IC3") (pin "9") (pinfunction "R2OUT_9") (pintype "output"))
    )
    (net (code "62") (name "unconnected-(IC3A-T2OUT-Pad7)") (class "Default")
      (node (ref "IC3") (pin "7") (pinfunction "T2OUT_7") (pintype "output"))
    )
    (net (code "63") (name "unconnected-(PDI_ATMEL-NC-Pad3)") (class "Default")
      (node (ref "PDI_ATMEL") (pin "3") (pinfunction "NC_3") (pintype "passive"))
    )
    (net (code "64") (name "unconnected-(PDI_ATMEL-NC.-Pad4)") (class "Default")
      (node (ref "PDI_ATMEL") (pin "4") (pinfunction "NC._4") (pintype "passive"))
    )
  )
)
